# DAC904.net
KiCad netlist of a schematic drawn in Altium Designer
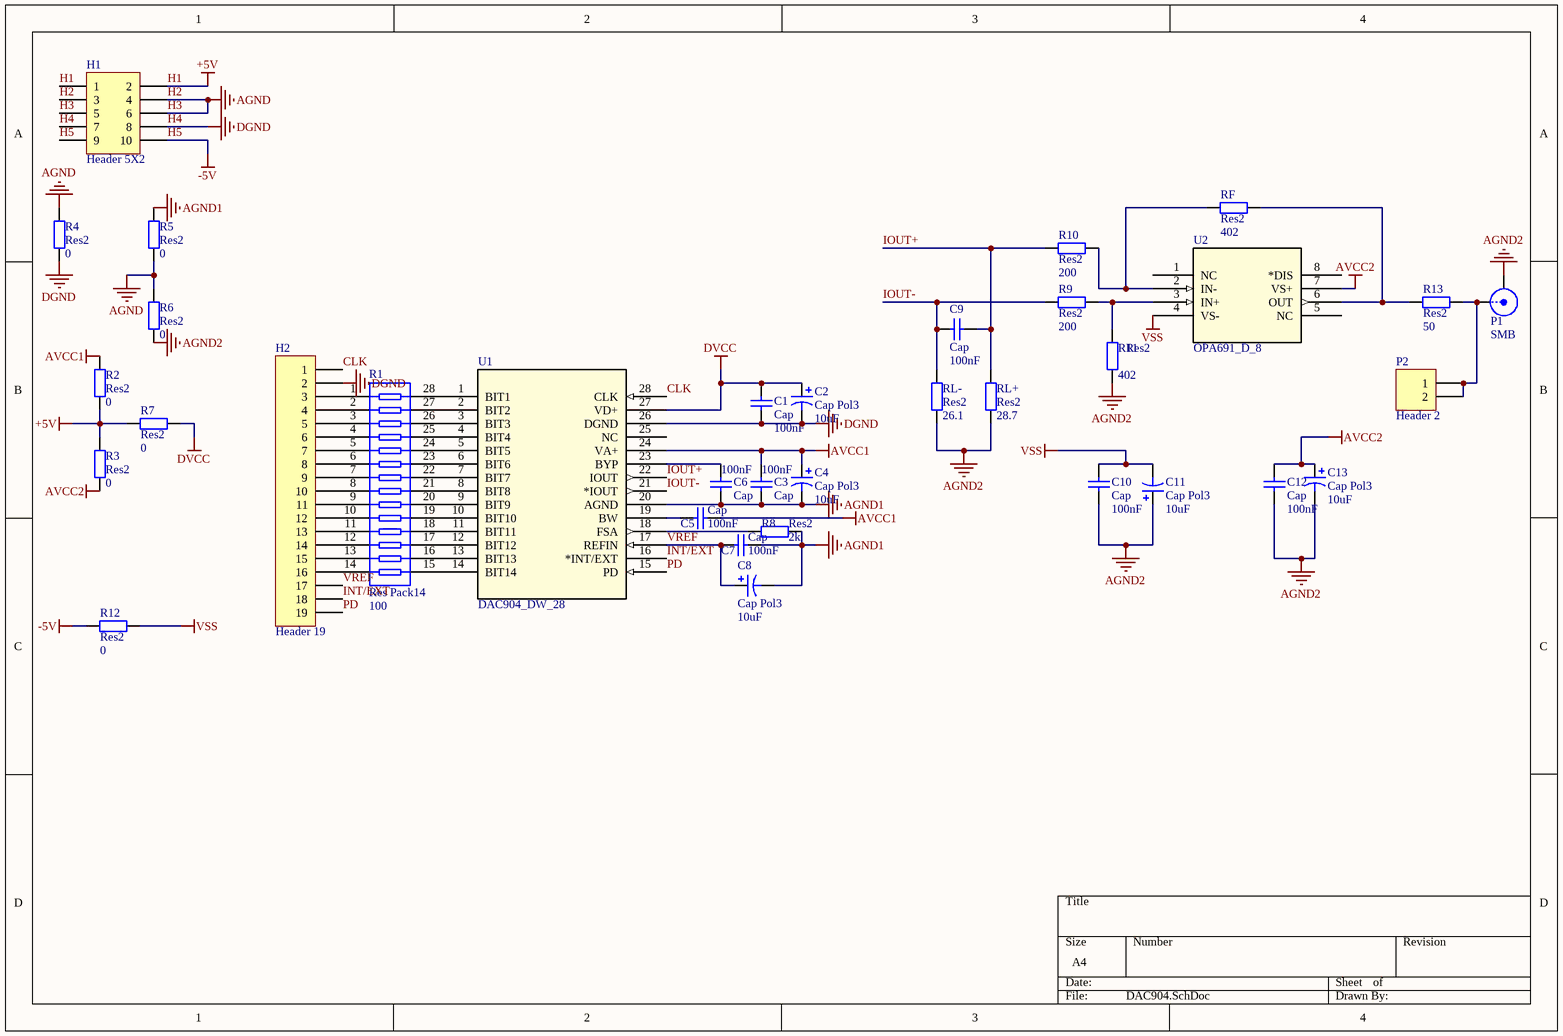
[diagram p0: DAC904.SchDoc]

(export (version "E")
  (design (tool "Eeschema 10.0.6"))
  (components
    (comp (ref "C1")
      (value "Cap")
      (footprint "C0805")
      (description "Capacitor")
      (fields (field (name "ALTIUM_VALUE") "100nF") (field (name "PUBLISHER") "Altium Limited"))
      (libsource (lib "Miscellaneous Devices") (part "Cap"))
    )
    (comp (ref "C2")
      (value "Cap Pol3")
      (footprint "CAP_SMD_3216")
      (description "Polarized Capacitor (Surface Mount)")
      (fields (field (name "ALTIUM_VALUE") "10uF") (field (name "PUBLISHER") "Altium Limited"))
      (libsource (lib "Miscellaneous Devices") (part "Cap Pol3"))
    )
    (comp (ref "C3")
      (value "Cap")
      (footprint "C0805")
      (description "Capacitor")
      (fields (field (name "ALTIUM_VALUE") "100nF") (field (name "PUBLISHER") "Altium Limited"))
      (libsource (lib "Miscellaneous Devices") (part "Cap"))
    )
    (comp (ref "C4")
      (value "Cap Pol3")
      (footprint "CAP_SMD_3216")
      (description "Polarized Capacitor (Surface Mount)")
      (fields (field (name "ALTIUM_VALUE") "10uF") (field (name "PUBLISHER") "Altium Limited"))
      (libsource (lib "Miscellaneous Devices") (part "Cap Pol3"))
    )
    (comp (ref "C5")
      (value "Cap")
      (footprint "C0805")
      (description "Capacitor")
      (fields (field (name "ALTIUM_VALUE") "100nF") (field (name "PUBLISHER") "Altium Limited"))
      (libsource (lib "Miscellaneous Devices") (part "Cap"))
    )
    (comp (ref "C6")
      (value "Cap")
      (footprint "C0805")
      (description "Capacitor")
      (fields (field (name "ALTIUM_VALUE") "100nF") (field (name "PUBLISHER") "Altium Limited"))
      (libsource (lib "Miscellaneous Devices") (part "Cap"))
    )
    (comp (ref "C7")
      (value "Cap")
      (footprint "C0805")
      (description "Capacitor")
      (fields (field (name "ALTIUM_VALUE") "100nF") (field (name "PUBLISHER") "Altium Limited"))
      (libsource (lib "Miscellaneous Devices") (part "Cap"))
    )
    (comp (ref "C8")
      (value "Cap Pol3")
      (footprint "CAP_SMD_3216")
      (description "Polarized Capacitor (Surface Mount)")
      (fields (field (name "ALTIUM_VALUE") "10uF") (field (name "PUBLISHER") "Altium Limited"))
      (libsource (lib "Miscellaneous Devices") (part "Cap Pol3"))
    )
    (comp (ref "C9")
      (value "Cap")
      (footprint "C0805")
      (description "Capacitor")
      (fields (field (name "ALTIUM_VALUE") "100nF") (field (name "PUBLISHER") "Altium Limited"))
      (libsource (lib "Miscellaneous Devices") (part "Cap"))
    )
    (comp (ref "C10")
      (value "Cap")
      (footprint "C0805")
      (description "Capacitor")
      (fields (field (name "ALTIUM_VALUE") "100nF") (field (name "PUBLISHER") "Altium Limited"))
      (libsource (lib "Miscellaneous Devices") (part "Cap"))
    )
    (comp (ref "C11")
      (value "Cap Pol3")
      (footprint "CAP_SMD_3216")
      (description "Polarized Capacitor (Surface Mount)")
      (fields (field (name "ALTIUM_VALUE") "10uF") (field (name "PUBLISHER") "Altium Limited"))
      (libsource (lib "Miscellaneous Devices") (part "Cap Pol3"))
    )
    (comp (ref "C12")
      (value "Cap")
      (footprint "C0805")
      (description "Capacitor")
      (fields (field (name "ALTIUM_VALUE") "100nF") (field (name "PUBLISHER") "Altium Limited"))
      (libsource (lib "Miscellaneous Devices") (part "Cap"))
    )
    (comp (ref "C13")
      (value "Cap Pol3")
      (footprint "CAP_SMD_3216")
      (description "Polarized Capacitor (Surface Mount)")
      (fields (field (name "ALTIUM_VALUE") "10uF") (field (name "PUBLISHER") "Altium Limited"))
      (libsource (lib "Miscellaneous Devices") (part "Cap Pol3"))
    )
    (comp (ref "H1")
      (value "Header 5X2")
      (footprint "HDR2X5")
      (description "Header, 5-Pin, Dual row")
      (fields (field (name "PUBLISHER") "Altium Limited"))
      (libsource (lib "Miscellaneous Connectors") (part "Header 5X2"))
    )
    (comp (ref "H2")
      (value "Header 19")
      (footprint "HDR1X19")
      (description "Header, 19-Pin")
      (fields (field (name "PUBLISHER") "Altium Limited"))
      (libsource (lib "Miscellaneous Connectors") (part "Header 19"))
    )
    (comp (ref "P1")
      (value "SMB")
      (footprint "SMB_V-RJ45")
      (description "SMB Straight Connector")
      (fields (field (name "PUBLISHER") "Altium Limited"))
      (libsource (lib "Miscellaneous Connectors") (part "SMB"))
    )
    (comp (ref "P2")
      (value "Header 2")
      (footprint "HDR1X2")
      (description "Header, 2-Pin")
      (fields (field (name "PUBLISHER") "Altium Limited"))
      (libsource (lib "Miscellaneous Connectors") (part "Header 2"))
    )
    (comp (ref "R1")
      (value "Res Pack14")
      (footprint "ResPack14")
      (description "Isolated Resistor Network")
      (fields (field (name "ALTIUM_VALUE") "100") (field (name "PUBLISHER") "Altium Limited"))
      (libsource (lib "Miscellaneous Devices_add") (part "Res Pack14"))
    )
    (comp (ref "R2")
      (value "Res2")
      (footprint "6-0805_N")
      (description "Resistor")
      (fields (field (name "ALTIUM_VALUE") "0") (field (name "PUBLISHER") "Altium Limited"))
      (libsource (lib "Miscellaneous Devices_add") (part "Res2"))
    )
    (comp (ref "R3")
      (value "Res2")
      (footprint "6-0805_N")
      (description "Resistor")
      (fields (field (name "ALTIUM_VALUE") "0") (field (name "PUBLISHER") "Altium Limited"))
      (libsource (lib "Miscellaneous Devices_add") (part "Res2"))
    )
    (comp (ref "R4")
      (value "Res2")
      (footprint "6-0805_N")
      (description "Resistor")
      (fields (field (name "ALTIUM_VALUE") "0") (field (name "PUBLISHER") "Altium Limited"))
      (libsource (lib "") (part "Res2_2"))
    )
    (comp (ref "R5")
      (value "Res2")
      (footprint "6-0805_N")
      (description "Resistor")
      (fields (field (name "ALTIUM_VALUE") "0") (field (name "PUBLISHER") "Altium Limited"))
      (libsource (lib "Miscellaneous Devices_add") (part "Res2"))
    )
    (comp (ref "R6")
      (value "Res2")
      (footprint "6-0805_N")
      (description "Resistor")
      (fields (field (name "ALTIUM_VALUE") "0") (field (name "PUBLISHER") "Altium Limited"))
      (libsource (lib "Miscellaneous Devices_add") (part "Res2"))
    )
    (comp (ref "R7")
      (value "Res2")
      (footprint "6-0805_N")
      (description "Resistor")
      (fields (field (name "ALTIUM_VALUE") "0") (field (name "PUBLISHER") "Altium Limited"))
      (libsource (lib "") (part "Res2_1"))
    )
    (comp (ref "R8")
      (value "Res2")
      (footprint "6-0805_N")
      (description "Resistor")
      (fields (field (name "ALTIUM_VALUE") "2k") (field (name "PUBLISHER") "Altium Limited"))
      (libsource (lib "") (part "Res2_1"))
    )
    (comp (ref "R9")
      (value "Res2")
      (footprint "6-0805_N")
      (description "Resistor")
      (fields (field (name "ALTIUM_VALUE") "200") (field (name "PUBLISHER") "Altium Limited"))
      (libsource (lib "") (part "Res2_1"))
    )
    (comp (ref "R10")
      (value "Res2")
      (footprint "6-0805_N")
      (description "Resistor")
      (fields (field (name "ALTIUM_VALUE") "200") (field (name "PUBLISHER") "Altium Limited"))
      (libsource (lib "") (part "Res2_1"))
    )
    (comp (ref "R11")
      (value "Res2")
      (footprint "6-0805_N")
      (description "Resistor")
      (fields (field (name "ALTIUM_VALUE") "402") (field (name "PUBLISHER") "Altium Limited"))
      (libsource (lib "") (part "Res2_2"))
    )
    (comp (ref "R12")
      (value "Res2")
      (footprint "6-0805_N")
      (description "Resistor")
      (fields (field (name "ALTIUM_VALUE") "0") (field (name "PUBLISHER") "Altium Limited"))
      (libsource (lib "") (part "Res2_1"))
    )
    (comp (ref "R13")
      (value "Res2")
      (footprint "6-0805_N")
      (description "Resistor")
      (fields (field (name "ALTIUM_VALUE") "50") (field (name "PUBLISHER") "Altium Limited"))
      (libsource (lib "") (part "Res2_1"))
    )
    (comp (ref "RF")
      (value "Res2")
      (footprint "6-0805_N")
      (description "Resistor")
      (fields (field (name "ALTIUM_VALUE") "402") (field (name "PUBLISHER") "Altium Limited"))
      (libsource (lib "") (part "Res2_1"))
    )
    (comp (ref "RL+")
      (value "Res2")
      (footprint "6-0805_N")
      (description "Resistor")
      (fields (field (name "ALTIUM_VALUE") "28.7") (field (name "PUBLISHER") "Altium Limited"))
      (libsource (lib "") (part "Res2_2"))
    )
    (comp (ref "RL-")
      (value "Res2")
      (footprint "6-0805_N")
      (description "Resistor")
      (fields (field (name "ALTIUM_VALUE") "26.1") (field (name "PUBLISHER") "Altium Limited"))
      (libsource (lib "") (part "Res2_2"))
    )
    (comp (ref "U1")
      (value "DAC904_DW_28")
      (footprint "PW28")
      (description "Imported")
      (fields (field (name "MANUFACTURER") "Texas Instruments") (field (name "GENERIC_PART_NUMBER") "DAC904"))
      (libsource (lib "SOIC28") (part "DAC904_DW_28"))
    )
    (comp (ref "U2")
      (value "OPA691_D_8")
      (footprint "D8")
      (description "Imported")
      (fields (field (name "MANUFACTURER") "Texas Instruments") (field (name "GENERIC_PART_NUMBER") "OPA691"))
      (libsource (lib "SOP8") (part "OPA691_D_8"))
    )
  )
  (nets
    (net (code "1") (name "+5V") (class "Default")
      (node (ref "H1") (pin "1") (pinfunction "1_1") (pintype "passive"))
      (node (ref "H1") (pin "2") (pinfunction "2_2") (pintype "passive"))
      (node (ref "R2") (pin "1") (pinfunction "1_1") (pintype "passive"))
      (node (ref "R3") (pin "2") (pinfunction "2_2") (pintype "passive"))
      (node (ref "R7") (pin "2") (pinfunction "2_2") (pintype "passive"))
    )
    (net (code "2") (name "-5V") (class "Default")
      (node (ref "H1") (pin "10") (pinfunction "10_10") (pintype "passive"))
      (node (ref "H1") (pin "9") (pinfunction "9_9") (pintype "passive"))
      (node (ref "R12") (pin "2") (pinfunction "2_2") (pintype "passive"))
    )
    (net (code "3") (name "/CLK") (class "Default")
      (node (ref "H2") (pin "1") (pinfunction "1_1") (pintype "passive"))
      (node (ref "U1") (pin "28") (pinfunction "CLK_28") (pintype "input"))
    )
    (net (code "4") (name "/INT{slash}EXT") (class "Default")
      (node (ref "H2") (pin "18") (pinfunction "18_18") (pintype "passive"))
      (node (ref "U1") (pin "16") (pinfunction "*INT/EXT_16") (pintype "passive"))
    )
    (net (code "5") (name "/IOUT+") (class "Default")
      (node (ref "C9") (pin "1") (pinfunction "1_1") (pintype "passive"))
      (node (ref "R10") (pin "2") (pinfunction "2_2") (pintype "passive"))
      (node (ref "RL+") (pin "1") (pinfunction "1_1") (pintype "passive"))
      (node (ref "U1") (pin "22") (pinfunction "IOUT_22") (pintype "output"))
    )
    (net (code "6") (name "/IOUT-") (class "Default")
      (node (ref "C9") (pin "2") (pinfunction "2_2") (pintype "passive"))
      (node (ref "R9") (pin "2") (pinfunction "2_2") (pintype "passive"))
      (node (ref "RL-") (pin "1") (pinfunction "1_1") (pintype "passive"))
      (node (ref "U1") (pin "21") (pinfunction "*IOUT_21") (pintype "output"))
    )
    (net (code "7") (name "/PD") (class "Default")
      (node (ref "H2") (pin "19") (pinfunction "19_19") (pintype "passive"))
      (node (ref "U1") (pin "15") (pinfunction "PD_15") (pintype "input"))
    )
    (net (code "8") (name "/VREF") (class "Default")
      (node (ref "C7") (pin "2") (pinfunction "2_2") (pintype "passive"))
      (node (ref "C8") (pin "1") (pinfunction "1_1") (pintype "passive"))
      (node (ref "H2") (pin "17") (pinfunction "17_17") (pintype "passive"))
      (node (ref "U1") (pin "17") (pinfunction "REFIN_17") (pintype "input"))
    )
    (net (code "9") (name "AGND") (class "Default")
      (node (ref "H1") (pin "3") (pinfunction "3_3") (pintype "passive"))
      (node (ref "H1") (pin "4") (pinfunction "4_4") (pintype "passive"))
      (node (ref "H1") (pin "5") (pinfunction "5_5") (pintype "passive"))
      (node (ref "H1") (pin "6") (pinfunction "6_6") (pintype "passive"))
      (node (ref "R4") (pin "1") (pinfunction "1_1") (pintype "passive"))
      (node (ref "R5") (pin "1") (pinfunction "1_1") (pintype "passive"))
      (node (ref "R6") (pin "2") (pinfunction "2_2") (pintype "passive"))
    )
    (net (code "10") (name "AGND1") (class "Default")
      (node (ref "C3") (pin "1") (pinfunction "1_1") (pintype "passive"))
      (node (ref "C4") (pin "2") (pinfunction "2_2") (pintype "passive"))
      (node (ref "C6") (pin "2") (pinfunction "2_2") (pintype "passive"))
      (node (ref "C7") (pin "1") (pinfunction "1_1") (pintype "passive"))
      (node (ref "C8") (pin "2") (pinfunction "2_2") (pintype "passive"))
      (node (ref "R5") (pin "2") (pinfunction "2_2") (pintype "passive"))
      (node (ref "R8") (pin "1") (pinfunction "1_1") (pintype "passive"))
      (node (ref "U1") (pin "20") (pinfunction "AGND_20") (pintype "power_in"))
    )
    (net (code "11") (name "AGND2") (class "Default")
      (node (ref "C10") (pin "1") (pinfunction "1_1") (pintype "passive"))
      (node (ref "C11") (pin "1") (pinfunction "1_1") (pintype "passive"))
      (node (ref "C12") (pin "1") (pinfunction "1_1") (pintype "passive"))
      (node (ref "C13") (pin "2") (pinfunction "2_2") (pintype "passive"))
      (node (ref "P1") (pin "2") (pinfunction "Y_2") (pintype "passive"))
      (node (ref "R11") (pin "2") (pinfunction "2_2") (pintype "passive"))
      (node (ref "R6") (pin "1") (pinfunction "1_1") (pintype "passive"))
      (node (ref "RL+") (pin "2") (pinfunction "2_2") (pintype "passive"))
      (node (ref "RL-") (pin "2") (pinfunction "2_2") (pintype "passive"))
    )
    (net (code "12") (name "AVCC1") (class "Default")
      (node (ref "C3") (pin "2") (pinfunction "2_2") (pintype "passive"))
      (node (ref "C4") (pin "1") (pinfunction "1_1") (pintype "passive"))
      (node (ref "C5") (pin "1") (pinfunction "1_1") (pintype "passive"))
      (node (ref "R2") (pin "2") (pinfunction "2_2") (pintype "passive"))
      (node (ref "U1") (pin "24") (pinfunction "VA+_24") (pintype "power_in"))
    )
    (net (code "13") (name "AVCC2") (class "Default")
      (node (ref "C12") (pin "2") (pinfunction "2_2") (pintype "passive"))
      (node (ref "C13") (pin "1") (pinfunction "1_1") (pintype "passive"))
      (node (ref "R3") (pin "1") (pinfunction "1_1") (pintype "passive"))
      (node (ref "U2") (pin "7") (pinfunction "VS+_7") (pintype "power_in"))
    )
    (net (code "14") (name "DGND") (class "Default")
      (node (ref "C1") (pin "1") (pinfunction "1_1") (pintype "passive"))
      (node (ref "C2") (pin "2") (pinfunction "2_2") (pintype "passive"))
      (node (ref "H1") (pin "7") (pinfunction "7_7") (pintype "passive"))
      (node (ref "H1") (pin "8") (pinfunction "8_8") (pintype "passive"))
      (node (ref "H2") (pin "2") (pinfunction "2_2") (pintype "passive"))
      (node (ref "R4") (pin "2") (pinfunction "2_2") (pintype "passive"))
      (node (ref "U1") (pin "26") (pinfunction "DGND_26") (pintype "power_in"))
    )
    (net (code "15") (name "DVCC") (class "Default")
      (node (ref "C1") (pin "2") (pinfunction "2_2") (pintype "passive"))
      (node (ref "C2") (pin "1") (pinfunction "1_1") (pintype "passive"))
      (node (ref "R7") (pin "1") (pinfunction "1_1") (pintype "passive"))
      (node (ref "U1") (pin "27") (pinfunction "VD+_27") (pintype "power_in"))
    )
    (net (code "16") (name "Net-(H2-Pad3)") (class "Default")
      (node (ref "H2") (pin "3") (pinfunction "3_3") (pintype "passive"))
      (node (ref "R1") (pin "1") (pinfunction "1_1") (pintype "passive"))
    )
    (net (code "17") (name "Net-(H2-Pad4)") (class "Default")
      (node (ref "H2") (pin "4") (pinfunction "4_4") (pintype "passive"))
      (node (ref "R1") (pin "2") (pinfunction "2_2") (pintype "passive"))
    )
    (net (code "18") (name "Net-(H2-Pad5)") (class "Default")
      (node (ref "H2") (pin "5") (pinfunction "5_5") (pintype "passive"))
      (node (ref "R1") (pin "3") (pinfunction "3_3") (pintype "passive"))
    )
    (net (code "19") (name "Net-(H2-Pad6)") (class "Default")
      (node (ref "H2") (pin "6") (pinfunction "6_6") (pintype "passive"))
      (node (ref "R1") (pin "4") (pinfunction "4_4") (pintype "passive"))
    )
    (net (code "20") (name "Net-(H2-Pad7)") (class "Default")
      (node (ref "H2") (pin "7") (pinfunction "7_7") (pintype "passive"))
      (node (ref "R1") (pin "5") (pinfunction "5_5") (pintype "passive"))
    )
    (net (code "21") (name "Net-(H2-Pad8)") (class "Default")
      (node (ref "H2") (pin "8") (pinfunction "8_8") (pintype "passive"))
      (node (ref "R1") (pin "6") (pinfunction "6_6") (pintype "passive"))
    )
    (net (code "22") (name "Net-(H2-Pad9)") (class "Default")
      (node (ref "H2") (pin "9") (pinfunction "9_9") (pintype "passive"))
      (node (ref "R1") (pin "7") (pinfunction "7_7") (pintype "passive"))
    )
    (net (code "23") (name "Net-(H2-Pad10)") (class "Default")
      (node (ref "H2") (pin "10") (pinfunction "10_10") (pintype "passive"))
      (node (ref "R1") (pin "8") (pinfunction "8_8") (pintype "passive"))
    )
    (net (code "24") (name "Net-(H2-Pad11)") (class "Default")
      (node (ref "H2") (pin "11") (pinfunction "11_11") (pintype "passive"))
      (node (ref "R1") (pin "9") (pinfunction "9_9") (pintype "passive"))
    )
    (net (code "25") (name "Net-(H2-Pad12)") (class "Default")
      (node (ref "H2") (pin "12") (pinfunction "12_12") (pintype "passive"))
      (node (ref "R1") (pin "10") (pinfunction "10_10") (pintype "passive"))
    )
    (net (code "26") (name "Net-(H2-Pad13)") (class "Default")
      (node (ref "H2") (pin "13") (pinfunction "13_13") (pintype "passive"))
      (node (ref "R1") (pin "11") (pinfunction "11_11") (pintype "passive"))
    )
    (net (code "27") (name "Net-(H2-Pad14)") (class "Default")
      (node (ref "H2") (pin "14") (pinfunction "14_14") (pintype "passive"))
      (node (ref "R1") (pin "12") (pinfunction "12_12") (pintype "passive"))
    )
    (net (code "28") (name "Net-(H2-Pad15)") (class "Default")
      (node (ref "H2") (pin "15") (pinfunction "15_15") (pintype "passive"))
      (node (ref "R1") (pin "13") (pinfunction "13_13") (pintype "passive"))
    )
    (net (code "29") (name "Net-(H2-Pad16)") (class "Default")
      (node (ref "H2") (pin "16") (pinfunction "16_16") (pintype "passive"))
      (node (ref "R1") (pin "14") (pinfunction "14_14") (pintype "passive"))
    )
    (net (code "30") (name "Net-(P1-X)") (class "Default")
      (node (ref "P1") (pin "1") (pinfunction "X_1") (pintype "passive"))
      (node (ref "P2") (pin "1") (pinfunction "1_1") (pintype "passive"))
      (node (ref "P2") (pin "2") (pinfunction "2_2") (pintype "passive"))
      (node (ref "R13") (pin "1") (pinfunction "1_1") (pintype "passive"))
    )
    (net (code "31") (name "Net-(U1-BIT1)") (class "Default")
      (node (ref "R1") (pin "28") (pinfunction "28_28") (pintype "passive"))
      (node (ref "U1") (pin "1") (pinfunction "BIT1_1") (pintype "passive"))
    )
    (net (code "32") (name "Net-(U1-BIT2)") (class "Default")
      (node (ref "R1") (pin "27") (pinfunction "27_27") (pintype "passive"))
      (node (ref "U1") (pin "2") (pinfunction "BIT2_2") (pintype "passive"))
    )
    (net (code "33") (name "Net-(U1-BIT3)") (class "Default")
      (node (ref "R1") (pin "26") (pinfunction "26_26") (pintype "passive"))
      (node (ref "U1") (pin "3") (pinfunction "BIT3_3") (pintype "passive"))
    )
    (net (code "34") (name "Net-(U1-BIT4)") (class "Default")
      (node (ref "R1") (pin "25") (pinfunction "25_25") (pintype "passive"))
      (node (ref "U1") (pin "4") (pinfunction "BIT4_4") (pintype "passive"))
    )
    (net (code "35") (name "Net-(U1-BIT5)") (class "Default")
      (node (ref "R1") (pin "24") (pinfunction "24_24") (pintype "passive"))
      (node (ref "U1") (pin "5") (pinfunction "BIT5_5") (pintype "passive"))
    )
    (net (code "36") (name "Net-(U1-BIT6)") (class "Default")
      (node (ref "R1") (pin "23") (pinfunction "23_23") (pintype "passive"))
      (node (ref "U1") (pin "6") (pinfunction "BIT6_6") (pintype "passive"))
    )
    (net (code "37") (name "Net-(U1-BIT7)") (class "Default")
      (node (ref "R1") (pin "22") (pinfunction "22_22") (pintype "passive"))
      (node (ref "U1") (pin "7") (pinfunction "BIT7_7") (pintype "passive"))
    )
    (net (code "38") (name "Net-(U1-BIT8)") (class "Default")
      (node (ref "R1") (pin "21") (pinfunction "21_21") (pintype "passive"))
      (node (ref "U1") (pin "8") (pinfunction "BIT8_8") (pintype "passive"))
    )
    (net (code "39") (name "Net-(U1-BIT9)") (class "Default")
      (node (ref "R1") (pin "20") (pinfunction "20_20") (pintype "passive"))
      (node (ref "U1") (pin "9") (pinfunction "BIT9_9") (pintype "passive"))
    )
    (net (code "40") (name "Net-(U1-BIT10)") (class "Default")
      (node (ref "R1") (pin "19") (pinfunction "19_19") (pintype "passive"))
      (node (ref "U1") (pin "10") (pinfunction "BIT10_10") (pintype "passive"))
    )
    (net (code "41") (name "Net-(U1-BIT11)") (class "Default")
      (node (ref "R1") (pin "18") (pinfunction "18_18") (pintype "passive"))
      (node (ref "U1") (pin "11") (pinfunction "BIT11_11") (pintype "passive"))
    )
    (net (code "42") (name "Net-(U1-BIT12)") (class "Default")
      (node (ref "R1") (pin "17") (pinfunction "17_17") (pintype "passive"))
      (node (ref "U1") (pin "12") (pinfunction "BIT12_12") (pintype "passive"))
    )
    (net (code "43") (name "Net-(U1-BIT13)") (class "Default")
      (node (ref "R1") (pin "16") (pinfunction "16_16") (pintype "passive"))
      (node (ref "U1") (pin "13") (pinfunction "BIT13_13") (pintype "passive"))
    )
    (net (code "44") (name "Net-(U1-BIT14)") (class "Default")
      (node (ref "R1") (pin "15") (pinfunction "15_15") (pintype "passive"))
      (node (ref "U1") (pin "14") (pinfunction "BIT14_14") (pintype "passive"))
    )
    (net (code "45") (name "Net-(U1-BW)") (class "Default")
      (node (ref "C5") (pin "2") (pinfunction "2_2") (pintype "passive"))
      (node (ref "U1") (pin "19") (pinfunction "BW_19") (pintype "passive"))
    )
    (net (code "46") (name "Net-(U1-BYP)") (class "Default")
      (node (ref "C6") (pin "1") (pinfunction "1_1") (pintype "passive"))
      (node (ref "U1") (pin "23") (pinfunction "BYP_23") (pintype "passive"))
    )
    (net (code "47") (name "Net-(U1-FSA)") (class "Default")
      (node (ref "R8") (pin "2") (pinfunction "2_2") (pintype "passive"))
      (node (ref "U1") (pin "18") (pinfunction "FSA_18") (pintype "output"))
    )
    (net (code "48") (name "Net-(U2-IN+)") (class "Default")
      (node (ref "R11") (pin "1") (pinfunction "1_1") (pintype "passive"))
      (node (ref "R9") (pin "1") (pinfunction "1_1") (pintype "passive"))
      (node (ref "U2") (pin "3") (pinfunction "IN+_3") (pintype "input"))
    )
    (net (code "49") (name "Net-(U2-IN-)") (class "Default")
      (node (ref "R10") (pin "1") (pinfunction "1_1") (pintype "passive"))
      (node (ref "RF") (pin "2") (pinfunction "2_2") (pintype "passive"))
      (node (ref "U2") (pin "2") (pinfunction "IN-_2") (pintype "input"))
    )
    (net (code "50") (name "Net-(U2-OUT)") (class "Default")
      (node (ref "R13") (pin "2") (pinfunction "2_2") (pintype "passive"))
      (node (ref "RF") (pin "1") (pinfunction "1_1") (pintype "passive"))
      (node (ref "U2") (pin "6") (pinfunction "OUT_6") (pintype "output"))
    )
    (net (code "51") (name "VSS") (class "Default")
      (node (ref "C10") (pin "2") (pinfunction "2_2") (pintype "passive"))
      (node (ref "C11") (pin "2") (pinfunction "2_2") (pintype "passive"))
      (node (ref "R12") (pin "1") (pinfunction "1_1") (pintype "passive"))
      (node (ref "U2") (pin "4") (pinfunction "VS-_4") (pintype "power_in"))
    )
    (net (code "52") (name "unconnected-(U1-NC-Pad25)") (class "Default")
      (node (ref "U1") (pin "25") (pinfunction "NC_25") (pintype "passive"))
    )
    (net (code "53") (name "unconnected-(U2-*DIS-Pad8)") (class "Default")
      (node (ref "U2") (pin "8") (pinfunction "*DIS_8") (pintype "passive"))
    )
    (net (code "54") (name "unconnected-(U2-NC-Pad1)") (class "Default")
      (node (ref "U2") (pin "1") (pinfunction "NC_1") (pintype "passive"))
    )
    (net (code "55") (name "unconnected-(U2-NC-Pad5)") (class "Default")
      (node (ref "U2") (pin "5") (pinfunction "NC_5") (pintype "passive"))
    )
  )
)
